# sd.net
KiCad netlist of a schematic drawn in Altium Designer
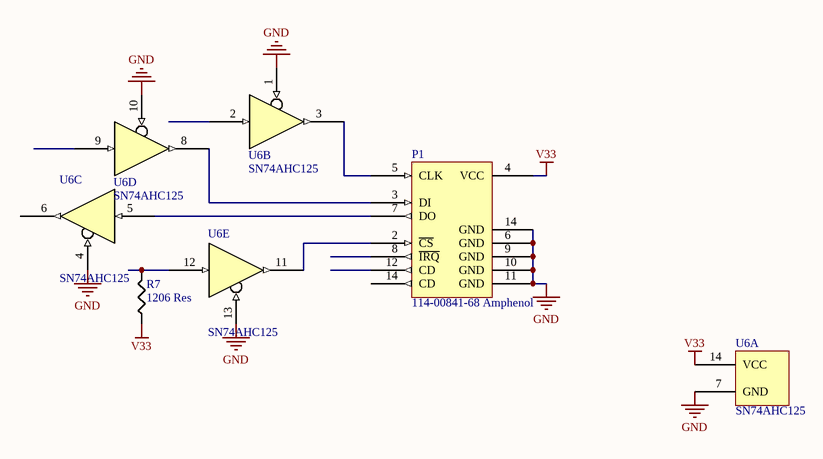
[diagram p0: sd.SchDoc]

(export (version "E")
  (design (tool "Eeschema 10.0.6"))
  (components
    (comp (ref "P1")
      (value "114-00841-68 Amphenol")
      (footprint "Final Board uSD")
      (description "MicroSD Card Slot")
      (libsource (lib "schlibLS") (part "uSD - 101-00660"))
    )
    (comp (ref "R7")
      (value "1206 Res")
      (footprint "RESC3115X06M")
      (libsource (lib "schlibLS") (part "1206 Resistor"))
    )
    (comp (ref "U6")
      (value "SN74AHC125")
      (footprint "DIP14")
      (description "Quad Input Buffer")
      (libsource (lib "") (part "SN74AHC125_1"))
    )
  )
  (nets
    (net (code "1") (name "GND") (class "Default")
      (node (ref "P1") (pin "10") (pinfunction "GND_10") (pintype "power_in"))
      (node (ref "P1") (pin "11") (pinfunction "GND_11") (pintype "power_in"))
      (node (ref "P1") (pin "14") (pinfunction "GND_14") (pintype "passive"))
      (node (ref "P1") (pin "6") (pinfunction "GND_6") (pintype "power_in"))
      (node (ref "P1") (pin "9") (pinfunction "GND_9") (pintype "power_in"))
      (node (ref "U6") (pin "1") (pinfunction "1~{OE}_1") (pintype "input"))
      (node (ref "U6") (pin "10") (pinfunction "3~{OE}_10") (pintype "input"))
      (node (ref "U6") (pin "13") (pinfunction "4~{OE}_13") (pintype "input"))
      (node (ref "U6") (pin "4") (pinfunction "2~{OE}_4") (pintype "input"))
      (node (ref "U6") (pin "7") (pinfunction "GND_7") (pintype "power_in"))
    )
    (net (code "2") (name "Net-(P1-CLK)") (class "Default")
      (node (ref "P1") (pin "5") (pinfunction "CLK_5") (pintype "input"))
      (node (ref "U6") (pin "3") (pinfunction "1Y_3") (pintype "output"))
    )
    (net (code "3") (name "Net-(P1-DI)") (class "Default")
      (node (ref "P1") (pin "3") (pinfunction "DI_3") (pintype "input"))
      (node (ref "U6") (pin "8") (pinfunction "3Y_8") (pintype "output"))
    )
    (net (code "4") (name "Net-(P1-DO)") (class "Default")
      (node (ref "P1") (pin "7") (pinfunction "DO_7") (pintype "output"))
      (node (ref "U6") (pin "5") (pinfunction "2A_5") (pintype "input"))
    )
    (net (code "5") (name "Net-(P1-~{CS})") (class "Default")
      (node (ref "P1") (pin "2") (pinfunction "~{CS}_2") (pintype "input"))
      (node (ref "U6") (pin "11") (pinfunction "4Y_11") (pintype "output"))
    )
    (net (code "6") (name "Net-(U6E-4A)") (class "Default")
      (node (ref "R7") (pin "2") (pinfunction "2_2") (pintype "passive"))
      (node (ref "U6") (pin "12") (pinfunction "4A_12") (pintype "input"))
    )
    (net (code "7") (name "V33") (class "Default")
      (node (ref "P1") (pin "4") (pinfunction "VCC_4") (pintype "power_in"))
      (node (ref "R7") (pin "1") (pinfunction "1_1") (pintype "passive"))
      (node (ref "U6") (pin "14") (pinfunction "VCC_14") (pintype "power_in"))
    )
    (net (code "8") (name "unconnected-(P1-CD-Pad12)") (class "Default")
      (node (ref "P1") (pin "12") (pinfunction "CD_12") (pintype "output"))
    )
    (net (code "9") (name "unconnected-(P1-CD-Pad14)") (class "Default")
      (node (ref "P1") (pin "14") (pinfunction "CD_14") (pintype "output"))
    )
    (net (code "10") (name "unconnected-(P1-NC-Pad1)") (class "Default")
      (node (ref "P1") (pin "1") (pinfunction "NC_1") (pintype "passive"))
    )
    (net (code "11") (name "unconnected-(P1-~{IRQ}-Pad8)") (class "Default")
      (node (ref "P1") (pin "8") (pinfunction "~{IRQ}_8") (pintype "output"))
    )
    (net (code "12") (name "unconnected-(U6B-1A-Pad2)") (class "Default")
      (node (ref "U6") (pin "2") (pinfunction "1A_2") (pintype "input"))
    )
    (net (code "13") (name "unconnected-(U6C-2Y-Pad6)") (class "Default")
      (node (ref "U6") (pin "6") (pinfunction "2Y_6") (pintype "output"))
    )
    (net (code "14") (name "unconnected-(U6D-3A-Pad9)") (class "Default")
      (node (ref "U6") (pin "9") (pinfunction "3A_9") (pintype "input"))
    )
  )
)
